# MCU-power.net
KiCad netlist of a schematic drawn in Altium Designer
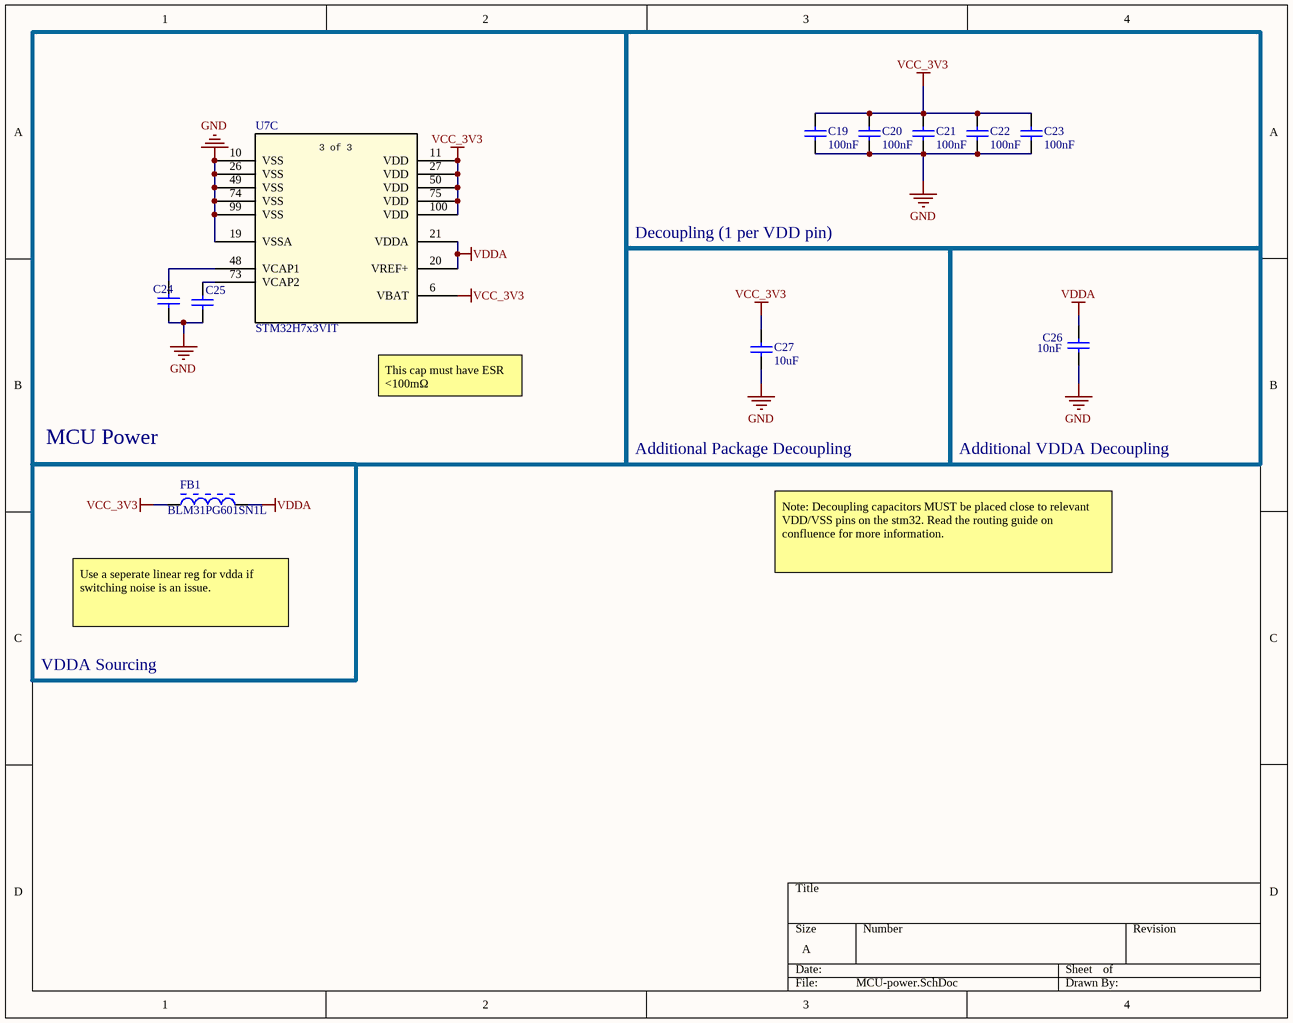
[diagram p0: MCU-power.SchDoc]

(export (version "E")
  (design (tool "Eeschema 10.0.6"))
  (components
    (comp (ref "C19")
      (value "100nF")
      (footprint "CAPC0603(1608)100_N")
      (description "CAP 100nF 10V ±10% 0603 (1608 Metric) Thickness 1mm SMD")
      (fields (field (name "TOLERANCE") "Â±10%"))
      (libsource (lib "Altium Content Vault") (part "CMP-1035-02580-1"))
    )
    (comp (ref "C20")
      (value "100nF")
      (footprint "CAPC0603(1608)100_N")
      (description "CAP 100nF 10V ±10% 0603 (1608 Metric) Thickness 1mm SMD")
      (fields (field (name "TOLERANCE") "Â±10%"))
      (libsource (lib "Altium Content Vault") (part "CAP"))
    )
    (comp (ref "C21")
      (value "100nF")
      (footprint "CAPC0603(1608)100_N")
      (description "CAP 100nF 10V ±10% 0603 (1608 Metric) Thickness 1mm SMD")
      (fields (field (name "TOLERANCE") "Â±10%"))
      (libsource (lib "Altium Content Vault") (part "CAP"))
    )
    (comp (ref "C22")
      (value "100nF")
      (footprint "CAPC0603(1608)100_N")
      (description "CAP 100nF 10V ±10% 0603 (1608 Metric) Thickness 1mm SMD")
      (fields (field (name "TOLERANCE") "Â±10%"))
      (libsource (lib "Altium Content Vault") (part "CAP"))
    )
    (comp (ref "C23")
      (value "100nF")
      (footprint "CAPC0603(1608)100_N")
      (description "CAP 100nF 10V ±10% 0603 (1608 Metric) Thickness 1mm SMD")
      (fields (field (name "TOLERANCE") "Â±10%"))
      (libsource (lib "Altium Content Vault") (part "CAP"))
    )
    (comp (ref "C24")
      (value "CAP 2.2uF 10V 0603(1608)")
      (footprint "CAPC0603(1608)100_N")
      (description "CAP 2.2uF 10V -20% to +80% 0603 (1608 Metric) Thickness 1mm SMD")
      (fields (field (name "TOLERANCE") "-20% to +80%"))
      (libsource (lib "Altium Content Vault") (part "CAP"))
    )
    (comp (ref "C25")
      (value "CAP 2.2uF 10V 0603(1608)")
      (footprint "CAPC0603(1608)100_N")
      (description "CAP 2.2uF 10V -20% to +80% 0603 (1608 Metric) Thickness 1mm SMD")
      (fields (field (name "TOLERANCE") "-20% to +80%"))
      (libsource (lib "Altium Content Vault") (part "CAP"))
    )
    (comp (ref "C26")
      (value "10nF")
      (footprint "CAPC0603(1608)100_M")
      (description "CAP 10nF 10V ±10% 0603 (1608 Metric) Thickness 1mm SMD")
      (fields (field (name "TOLERANCE") "Â±10%"))
      (libsource (lib "Altium Content Vault") (part "CAP"))
    )
    (comp (ref "C27")
      (value "10uF")
      (footprint "CAPC0603(1608)100_N")
      (description "CAP 10uF 10V ±10% 0603 (1608 Metric) Thickness 1mm SMD")
      (fields (field (name "TOLERANCE") "Â±10%"))
      (libsource (lib "Altium Content Vault") (part "CAP"))
    )
    (comp (ref "FB1")
      (value "BLM31PG601SN1L")
      (footprint "MURA-BLM31-B-CHIP-2_V")
      (fields (field (name "MANUFACTURER") "Murata"))
      (libsource (lib "Altium Content Vault") (part "MURA-FB-2"))
    )
    (comp (ref "U7")
      (value "STM32H7x3VIT")
      (footprint "LQFP100-14x14mm")
      (description "Imported")
      (fields
        (field (name "MANUFACTURER_PART_NUMBER") "stm32h7x3vit")
        (field (name "COPYRIGHT") "Copyright (C) 2016 Accelerated Designs. All rights reserved")
      )
      (libsource (lib "TAUV_Components") (part "STM32H7x3VIT"))
    )
  )
  (nets
    (net (code "1") (name "GND") (class "Default")
      (node (ref "C19") (pin "1") (pinfunction "1_1") (pintype "passive"))
      (node (ref "C20") (pin "1") (pinfunction "1_1") (pintype "passive"))
      (node (ref "C21") (pin "1") (pinfunction "1_1") (pintype "passive"))
      (node (ref "C22") (pin "1") (pinfunction "1_1") (pintype "passive"))
      (node (ref "C23") (pin "1") (pinfunction "1_1") (pintype "passive"))
      (node (ref "C24") (pin "1") (pinfunction "1_1") (pintype "passive"))
      (node (ref "C25") (pin "1") (pinfunction "1_1") (pintype "passive"))
      (node (ref "C26") (pin "2") (pinfunction "2_2") (pintype "passive"))
      (node (ref "C27") (pin "1") (pinfunction "1_1") (pintype "passive"))
      (node (ref "U7") (pin "10") (pinfunction "VSS_10") (pintype "power_in"))
      (node (ref "U7") (pin "19") (pinfunction "VSSA_19") (pintype "power_in"))
      (node (ref "U7") (pin "26") (pinfunction "VSS_26") (pintype "power_in"))
      (node (ref "U7") (pin "49") (pinfunction "VSS_49") (pintype "power_in"))
      (node (ref "U7") (pin "74") (pinfunction "VSS_74") (pintype "power_in"))
      (node (ref "U7") (pin "99") (pinfunction "VSS_99") (pintype "power_in"))
    )
    (net (code "2") (name "Net-(U7C-VCAP1)") (class "Default")
      (node (ref "C24") (pin "2") (pinfunction "2_2") (pintype "passive"))
      (node (ref "U7") (pin "48") (pinfunction "VCAP1_48") (pintype "power_in"))
    )
    (net (code "3") (name "Net-(U7C-VCAP2)") (class "Default")
      (node (ref "C25") (pin "2") (pinfunction "2_2") (pintype "passive"))
      (node (ref "U7") (pin "73") (pinfunction "VCAP2_73") (pintype "power_in"))
    )
    (net (code "4") (name "VCC_3V3") (class "Default")
      (node (ref "C19") (pin "2") (pinfunction "2_2") (pintype "passive"))
      (node (ref "C20") (pin "2") (pinfunction "2_2") (pintype "passive"))
      (node (ref "C21") (pin "2") (pinfunction "2_2") (pintype "passive"))
      (node (ref "C22") (pin "2") (pinfunction "2_2") (pintype "passive"))
      (node (ref "C23") (pin "2") (pinfunction "2_2") (pintype "passive"))
      (node (ref "C27") (pin "2") (pinfunction "2_2") (pintype "passive"))
      (node (ref "FB1") (pin "1") (pinfunction "1_1") (pintype "passive"))
      (node (ref "U7") (pin "100") (pinfunction "VDD_100") (pintype "power_in"))
      (node (ref "U7") (pin "11") (pinfunction "VDD_11") (pintype "power_in"))
      (node (ref "U7") (pin "27") (pinfunction "VDD_27") (pintype "power_in"))
      (node (ref "U7") (pin "50") (pinfunction "VDD_50") (pintype "power_in"))
      (node (ref "U7") (pin "6") (pinfunction "VBAT_6") (pintype "power_in"))
      (node (ref "U7") (pin "75") (pinfunction "VDD_75") (pintype "power_in"))
    )
    (net (code "5") (name "VDDA") (class "Default")
      (node (ref "C26") (pin "1") (pinfunction "1_1") (pintype "passive"))
      (node (ref "FB1") (pin "2") (pinfunction "2_2") (pintype "passive"))
      (node (ref "U7") (pin "20") (pinfunction "VREF+_20") (pintype "power_in"))
      (node (ref "U7") (pin "21") (pinfunction "VDDA_21") (pintype "power_in"))
    )
  )
)
